# power.net
KiCad netlist of a schematic drawn in Altium Designer
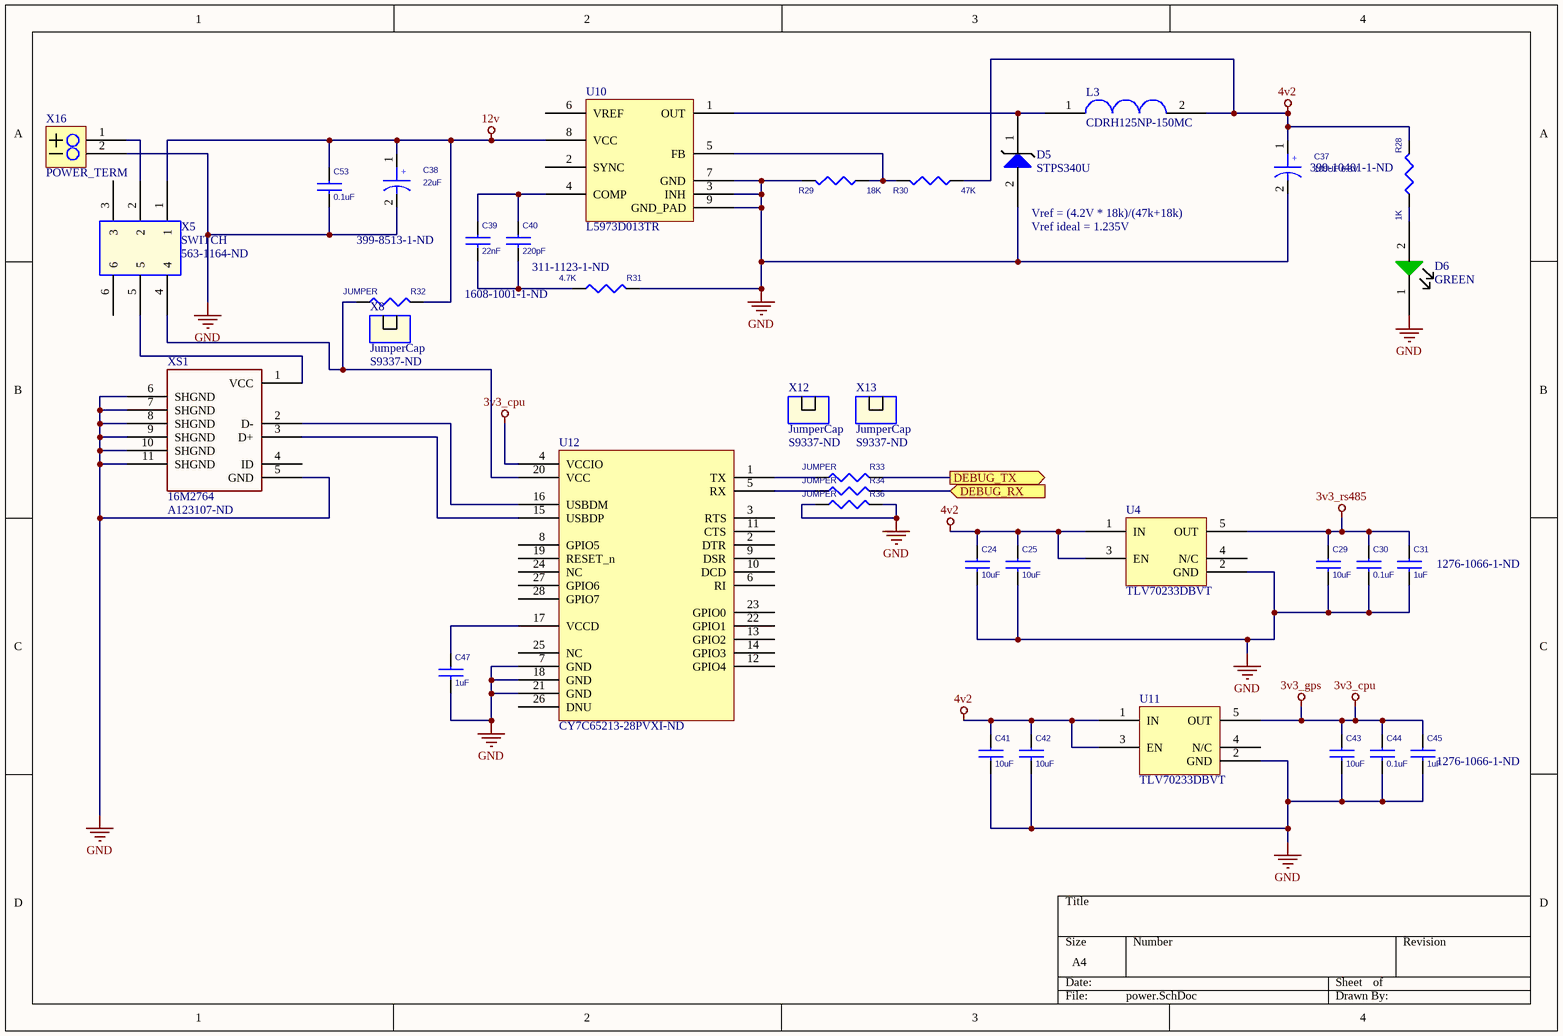
[diagram p0: power.SchDoc]

(export (version "E")
  (design (tool "Eeschema 10.0.6"))
  (components
    (comp (ref "C24")
      (value "10uF")
      (footprint "CAPC2012X09M")
      (description "CAP CER 10UF 16V 20% X5R 0805")
      (libsource (lib "Capacitors") (part "CAP_SMD_10UF_20%"))
    )
    (comp (ref "C25")
      (value "10uF")
      (footprint "CAPC2012X09M")
      (description "CAP CER 10UF 16V 20% X5R 0805")
      (libsource (lib "Capacitors") (part "CAP_SMD_10UF_20%"))
    )
    (comp (ref "C29")
      (value "10uF")
      (footprint "CAPC2012X09M")
      (description "CAP CER 10UF 16V 20% X5R 0805")
      (libsource (lib "Capacitors") (part "CAP_SMD_10UF_20%"))
    )
    (comp (ref "C30")
      (value "0.1uF")
      (footprint "CAPC2012X09M")
      (description "CAP CER 0.1UF 25V 10% X7R 0805")
      (libsource (lib "Capacitors") (part "CAP_SMD_0.1UF_10%"))
    )
    (comp (ref "C31")
      (value "1uF")
      (footprint "CAPC2012X09M")
      (description "MLCC; 1uF; 25V; X7R; ±10%; SMD; 0805;")
      (fields (field (name "SUPPLIER PART NUMBER 1") "1276-1066-1-ND"))
      (libsource (lib "Capacitors") (part "CAP_SMD_1uF_10%"))
    )
    (comp (ref "C37")
      (value "100UF 6.3V")
      (footprint "CAPMP6133X31N")
      (description "CAP 100uF; 6.3V; Case: C; ESR:150mOhm")
      (fields (field (name "SUPPLIER PART NUMBER 1") "399-10401-1-ND"))
      (libsource (lib "Capacitors") (part "CAP_SMD_100UF_10%"))
    )
    (comp (ref "C38")
      (value "22uF")
      (footprint "CAPMP7143X31N")
      (description "CAP SMD 35volts 22uF 10% ESR=300mOhms")
      (fields (field (name "SUPPLIER PART NUMBER 1") "399-8513-1-ND"))
      (libsource (lib "Capacitors") (part "CAP_SMD_22UF_10%"))
    )
    (comp (ref "C39")
      (value "22nF")
      (footprint "CAPC2012X09M")
      (description "CAP 22NF 50V 10% X7R 0805")
      (fields (field (name "SUPPLIER PART NUMBER 1") "1608-1001-1-ND"))
      (libsource (lib "Capacitors") (part "CAP_SMD_22nF_10%"))
    )
    (comp (ref "C40")
      (value "220pF")
      (footprint "CAPC2012X09M")
      (description "CAP 220PF 50V 10%  0805")
      (fields (field (name "SUPPLIER PART NUMBER 1") "311-1123-1-ND"))
      (libsource (lib "Capacitors") (part "CAP_SMD_220pF_10%"))
    )
    (comp (ref "C41")
      (value "10uF")
      (footprint "CAPC2012X09M")
      (description "CAP CER 10UF 16V 20% X5R 0805")
      (libsource (lib "Capacitors") (part "CAP_SMD_10UF_20%"))
    )
    (comp (ref "C42")
      (value "10uF")
      (footprint "CAPC2012X09M")
      (description "CAP CER 10UF 16V 20% X5R 0805")
      (libsource (lib "Capacitors") (part "CAP_SMD_10UF_20%"))
    )
    (comp (ref "C43")
      (value "10uF")
      (footprint "CAPC2012X09M")
      (description "CAP CER 10UF 16V 20% X5R 0805")
      (libsource (lib "Capacitors") (part "CAP_SMD_10UF_20%"))
    )
    (comp (ref "C44")
      (value "0.1uF")
      (footprint "CAPC2012X09M")
      (description "CAP CER 0.1UF 25V 10% X7R 0805")
      (libsource (lib "Capacitors") (part "CAP_SMD_0.1UF_10%"))
    )
    (comp (ref "C45")
      (value "1uF")
      (footprint "CAPC2012X09M")
      (description "MLCC; 1uF; 25V; X7R; ±10%; SMD; 0805;")
      (fields (field (name "SUPPLIER PART NUMBER 1") "1276-1066-1-ND"))
      (libsource (lib "Capacitors") (part "CAP_SMD_1uF_10%"))
    )
    (comp (ref "C47")
      (value "1uF")
      (footprint "CAPC2012X09M")
      (description "MLCC; 1uF; 25V; X7R; ±10%; SMD; 0805;")
      (libsource (lib "Capacitors") (part "CAP_SMD_1uF_10%"))
    )
    (comp (ref "C53")
      (value "0.1uF")
      (footprint "CAPC2012X09M")
      (description "CAP CER 0.1UF 25V 10% X7R 0805")
      (libsource (lib "Capacitors") (part "CAP_SMD_0.1UF_10%"))
    )
    (comp (ref "D5")
      (value "STPS340U")
      (footprint "SODFL535X265-2N")
      (description "DIODE, ZENER, 20V, 3W")
      (libsource (lib "Passive") (part "STPS340U"))
    )
    (comp (ref "D6")
      (value "GREEN")
      (footprint "DIOC2012X11N")
      (libsource (lib "Passive") (part "LED_GREEN"))
    )
    (comp (ref "L3")
      (value "CDRH125NP-150MC")
      (footprint "INDP123123X40N_SUMIDA")
      (libsource (lib "Passive") (part "IND_15uH_3.3A"))
    )
    (comp (ref "R28")
      (value "1K")
      (footprint "RESC2013X06M")
      (description "RES - 1K OHM, 5%, 1/8W, 0805 SMD")
      (libsource (lib "Resistors") (part "RES_SMD_1K_5%"))
    )
    (comp (ref "R29")
      (value "18K")
      (footprint "RESC2013X06M")
      (description "RES 18K OHM 1/8W 1% 0805 SMD")
      (libsource (lib "Resistors") (part "RES_SMD_18K_1%"))
    )
    (comp (ref "R30")
      (value "47K")
      (footprint "RESC2013X06M")
      (description "RES 47K OHM 1/8W 1% 0805")
      (libsource (lib "Resistors") (part "RES_SMD_47K_1%"))
    )
    (comp (ref "R31")
      (value "4.7K")
      (footprint "RESC2013X06M")
      (description "RES 4.7K OHM 1/8W 1% 0805 SMD")
      (libsource (lib "Resistors") (part "RES_SMD_4.7K_1%"))
    )
    (comp (ref "R32")
      (value "JUMPER")
      (footprint "RESC2013X06M_CMEASURE")
      (description "RES 0.0 OHM 1/8W JUMP 0805 SMD")
      (libsource (lib "Resistors") (part "RES_SMD_0_CURRENT"))
    )
    (comp (ref "R33")
      (value "JUMPER")
      (footprint "RESC2013X06M_CMEASURE")
      (description "RES 0.0 OHM 1/8W JUMP 0805 SMD")
      (libsource (lib "Resistors") (part "RES_SMD_0_CURRENT"))
    )
    (comp (ref "R34")
      (value "JUMPER")
      (footprint "RESC2013X06M_CMEASURE")
      (description "RES 0.0 OHM 1/8W JUMP 0805 SMD")
      (libsource (lib "Resistors") (part "RES_SMD_0_CURRENT"))
    )
    (comp (ref "R36")
      (value "JUMPER")
      (footprint "RESC2013X06M_CMEASURE")
      (description "RES 0.0 OHM 1/8W JUMP 0805 SMD")
      (libsource (lib "Resistors") (part "RES_SMD_0_CURRENT"))
    )
    (comp (ref "U4")
      (value "TLV70233DBVT")
      (footprint "SOT95P280X145-5M")
      (libsource (lib "TruthEar") (part "TLV70233DBVT"))
    )
    (comp (ref "U10")
      (value "L5973D013TR")
      (footprint "SOIC127P600X175_HS-9N")
      (description "IC REG BUCK ADJ 2.5A SOIC8")
      (libsource (lib "TruthEar") (part "L5973D013TR"))
    )
    (comp (ref "U11")
      (value "TLV70233DBVT")
      (footprint "SOT95P280X145-5M")
      (libsource (lib "TruthEar") (part "TLV70233DBVT"))
    )
    (comp (ref "U12")
      (value "CY7C65213")
      (footprint "SOP65P780X200-28M")
      (fields (field (name "SUPPLIER PART NUMBER 1") "CY7C65213-28PVXI-ND"))
      (libsource (lib "TruthEar") (part "CY7C65213"))
    )
    (comp (ref "X5")
      (value "SWITCH")
      (footprint "SWITCH")
      (fields (field (name "SUPPLIER PART NUMBER 1") "563-1164-ND"))
      (libsource (lib "TruthEar") (part "SWITCH"))
    )
    (comp (ref "X8")
      (value "JumperCap")
      (description "For BOM only")
      (fields (field (name "SUPPLIER PART NUMBER 1") "S9337-ND"))
      (libsource (lib "TruthEar") (part "JumperCap"))
    )
    (comp (ref "X12")
      (value "JumperCap")
      (description "For BOM only")
      (fields (field (name "SUPPLIER PART NUMBER 1") "S9337-ND"))
      (libsource (lib "TruthEar") (part "JumperCap"))
    )
    (comp (ref "X13")
      (value "JumperCap")
      (description "For BOM only")
      (fields (field (name "SUPPLIER PART NUMBER 1") "S9337-ND"))
      (libsource (lib "TruthEar") (part "JumperCap"))
    )
    (comp (ref "X16")
      (value "POWER_TERM")
      (footprint "PH5")
      (libsource (lib "Connectors") (part "POWER_TERM"))
    )
    (comp (ref "XS1")
      (value "16M2764")
      (footprint "USB_MINI_16M2764")
      (fields (field (name "SUPPLIER PART NUMBER 1") "A123107-ND"))
      (libsource (lib "Connectors") (part "USB_MINI_16M2764"))
    )
  )
  (nets
    (net (code "1") (name "/DEBUG_RX") (class "Default")
      (node (ref "R34") (pin "2") (pinfunction "2_2") (pintype "passive"))
    )
    (net (code "2") (name "/DEBUG_TX") (class "Default")
      (node (ref "R33") (pin "2") (pinfunction "2_2") (pintype "passive"))
    )
    (net (code "3") (name "3v3_cpu") (class "Default")
      (node (ref "C43") (pin "1") (pinfunction "1_1") (pintype "passive"))
      (node (ref "C44") (pin "1") (pinfunction "1_1") (pintype "passive"))
      (node (ref "C45") (pin "1") (pinfunction "1_1") (pintype "passive"))
      (node (ref "U11") (pin "5") (pinfunction "OUT_5") (pintype "passive"))
      (node (ref "U12") (pin "4") (pinfunction "VCCIO_4") (pintype "power_in"))
    )
    (net (code "4") (name "3v3_rs485") (class "Default")
      (node (ref "C29") (pin "1") (pinfunction "1_1") (pintype "passive"))
      (node (ref "C30") (pin "1") (pinfunction "1_1") (pintype "passive"))
      (node (ref "C31") (pin "1") (pinfunction "1_1") (pintype "passive"))
      (node (ref "U4") (pin "5") (pinfunction "OUT_5") (pintype "passive"))
    )
    (net (code "5") (name "4v2") (class "Default")
      (node (ref "C24") (pin "1") (pinfunction "1_1") (pintype "passive"))
      (node (ref "C25") (pin "1") (pinfunction "1_1") (pintype "passive"))
      (node (ref "C37") (pin "1") (pinfunction "1_1") (pintype "passive"))
      (node (ref "C41") (pin "1") (pinfunction "1_1") (pintype "passive"))
      (node (ref "C42") (pin "1") (pinfunction "1_1") (pintype "passive"))
      (node (ref "L3") (pin "2") (pinfunction "2_2") (pintype "passive"))
      (node (ref "R28") (pin "2") (pinfunction "2_2") (pintype "passive"))
      (node (ref "R30") (pin "1") (pinfunction "1_1") (pintype "passive"))
      (node (ref "U11") (pin "1") (pinfunction "IN_1") (pintype "passive"))
      (node (ref "U11") (pin "3") (pinfunction "EN_3") (pintype "passive"))
      (node (ref "U4") (pin "1") (pinfunction "IN_1") (pintype "passive"))
      (node (ref "U4") (pin "3") (pinfunction "EN_3") (pintype "passive"))
    )
    (net (code "6") (name "12v") (class "Default")
      (node (ref "C38") (pin "1") (pinfunction "1_1") (pintype "passive"))
      (node (ref "C53") (pin "1") (pinfunction "1_1") (pintype "passive"))
      (node (ref "R32") (pin "2") (pinfunction "2_2") (pintype "passive"))
      (node (ref "U10") (pin "8") (pinfunction "VCC_8") (pintype "passive"))
      (node (ref "X5") (pin "1") (pinfunction "1_1") (pintype "passive"))
    )
    (net (code "7") (name "GND") (class "Default")
      (node (ref "C24") (pin "2") (pinfunction "2_2") (pintype "passive"))
      (node (ref "C25") (pin "2") (pinfunction "2_2") (pintype "passive"))
      (node (ref "C29") (pin "2") (pinfunction "2_2") (pintype "passive"))
      (node (ref "C30") (pin "2") (pinfunction "2_2") (pintype "passive"))
      (node (ref "C31") (pin "2") (pinfunction "2_2") (pintype "passive"))
      (node (ref "C37") (pin "2") (pinfunction "2_2") (pintype "passive"))
      (node (ref "C38") (pin "2") (pinfunction "2_2") (pintype "passive"))
      (node (ref "C41") (pin "2") (pinfunction "2_2") (pintype "passive"))
      (node (ref "C42") (pin "2") (pinfunction "2_2") (pintype "passive"))
      (node (ref "C43") (pin "2") (pinfunction "2_2") (pintype "passive"))
      (node (ref "C44") (pin "2") (pinfunction "2_2") (pintype "passive"))
      (node (ref "C45") (pin "2") (pinfunction "2_2") (pintype "passive"))
      (node (ref "C47") (pin "2") (pinfunction "2_2") (pintype "passive"))
      (node (ref "C53") (pin "2") (pinfunction "2_2") (pintype "passive"))
      (node (ref "D5") (pin "2") (pinfunction "A_2") (pintype "passive"))
      (node (ref "D6") (pin "1") (pinfunction "C_1") (pintype "passive"))
      (node (ref "R29") (pin "2") (pinfunction "2_2") (pintype "passive"))
      (node (ref "R31") (pin "2") (pinfunction "2_2") (pintype "passive"))
      (node (ref "R36") (pin "1") (pinfunction "1_1") (pintype "passive"))
      (node (ref "R36") (pin "2") (pinfunction "2_2") (pintype "passive"))
      (node (ref "U10") (pin "3") (pinfunction "INH_3") (pintype "passive"))
      (node (ref "U10") (pin "7") (pinfunction "GND_7") (pintype "passive"))
      (node (ref "U10") (pin "9") (pinfunction "GND_PAD_9") (pintype "passive"))
      (node (ref "U11") (pin "2") (pinfunction "GND_2") (pintype "passive"))
      (node (ref "U12") (pin "18") (pinfunction "GND_18") (pintype "power_in"))
      (node (ref "U12") (pin "21") (pinfunction "GND_21") (pintype "power_in"))
      (node (ref "U12") (pin "7") (pinfunction "GND_7") (pintype "power_in"))
      (node (ref "U4") (pin "2") (pinfunction "GND_2") (pintype "passive"))
      (node (ref "X16") (pin "2") (pinfunction "2_2") (pintype "passive"))
      (node (ref "XS1") (pin "10") (pinfunction "SHGND_10") (pintype "passive"))
      (node (ref "XS1") (pin "11") (pinfunction "SHGND_11") (pintype "passive"))
      (node (ref "XS1") (pin "5") (pinfunction "GND_5") (pintype "passive"))
      (node (ref "XS1") (pin "6") (pinfunction "SHGND_6") (pintype "passive"))
      (node (ref "XS1") (pin "7") (pinfunction "SHGND_7") (pintype "passive"))
      (node (ref "XS1") (pin "8") (pinfunction "SHGND_8") (pintype "passive"))
      (node (ref "XS1") (pin "9") (pinfunction "SHGND_9") (pintype "passive"))
    )
    (net (code "8") (name "Net-(C39-Pad2)") (class "Default")
      (node (ref "C39") (pin "2") (pinfunction "2_2") (pintype "passive"))
      (node (ref "C40") (pin "2") (pinfunction "2_2") (pintype "passive"))
      (node (ref "R31") (pin "1") (pinfunction "1_1") (pintype "passive"))
    )
    (net (code "9") (name "Net-(D5-C)") (class "Default")
      (node (ref "D5") (pin "1") (pinfunction "C_1") (pintype "passive"))
      (node (ref "L3") (pin "1") (pinfunction "1_1") (pintype "passive"))
      (node (ref "U10") (pin "1") (pinfunction "OUT_1") (pintype "passive"))
    )
    (net (code "10") (name "Net-(D6-A)") (class "Default")
      (node (ref "D6") (pin "2") (pinfunction "A_2") (pintype "passive"))
      (node (ref "R28") (pin "1") (pinfunction "1_1") (pintype "passive"))
    )
    (net (code "11") (name "Net-(U10-COMP)") (class "Default")
      (node (ref "C39") (pin "1") (pinfunction "1_1") (pintype "passive"))
      (node (ref "C40") (pin "1") (pinfunction "1_1") (pintype "passive"))
      (node (ref "U10") (pin "4") (pinfunction "COMP_4") (pintype "passive"))
    )
    (net (code "12") (name "Net-(U10-FB)") (class "Default")
      (node (ref "R29") (pin "1") (pinfunction "1_1") (pintype "passive"))
      (node (ref "R30") (pin "2") (pinfunction "2_2") (pintype "passive"))
      (node (ref "U10") (pin "5") (pinfunction "FB_5") (pintype "passive"))
    )
    (net (code "13") (name "Net-(U12-RX)") (class "Default")
      (node (ref "R34") (pin "1") (pinfunction "1_1") (pintype "passive"))
      (node (ref "U12") (pin "5") (pinfunction "RX_5") (pintype "power_in"))
    )
    (net (code "14") (name "Net-(U12-TX)") (class "Default")
      (node (ref "R33") (pin "1") (pinfunction "1_1") (pintype "passive"))
      (node (ref "U12") (pin "1") (pinfunction "TX_1") (pintype "power_in"))
    )
    (net (code "15") (name "Net-(U12-USBDM)") (class "Default")
      (node (ref "U12") (pin "16") (pinfunction "USBDM_16") (pintype "power_in"))
      (node (ref "XS1") (pin "2") (pinfunction "D-_2") (pintype "passive"))
    )
    (net (code "16") (name "Net-(U12-USBDP)") (class "Default")
      (node (ref "U12") (pin "15") (pinfunction "USBDP_15") (pintype "power_in"))
      (node (ref "XS1") (pin "3") (pinfunction "D+_3") (pintype "passive"))
    )
    (net (code "17") (name "Net-(U12-VCC)") (class "Default")
      (node (ref "R32") (pin "1") (pinfunction "1_1") (pintype "passive"))
      (node (ref "U12") (pin "20") (pinfunction "VCC_20") (pintype "power_in"))
      (node (ref "X5") (pin "4") (pinfunction "4_4") (pintype "passive"))
    )
    (net (code "18") (name "Net-(U12-VCCD)") (class "Default")
      (node (ref "C47") (pin "1") (pinfunction "1_1") (pintype "passive"))
      (node (ref "U12") (pin "17") (pinfunction "VCCD_17") (pintype "power_in"))
    )
    (net (code "19") (name "Net-(X16-Pad1)") (class "Default")
      (node (ref "X16") (pin "1") (pinfunction "1_1") (pintype "passive"))
      (node (ref "X5") (pin "2") (pinfunction "2_2") (pintype "passive"))
    )
    (net (code "20") (name "Net-(XS1-VCC)") (class "Default")
      (node (ref "X5") (pin "5") (pinfunction "5_5") (pintype "passive"))
      (node (ref "XS1") (pin "1") (pinfunction "VCC_1") (pintype "passive"))
    )
    (net (code "21") (name "unconnected-(U4-N{slash}C-Pad4)") (class "Default")
      (node (ref "U4") (pin "4") (pinfunction "N/C_4") (pintype "passive"))
    )
    (net (code "22") (name "unconnected-(U10-SYNC-Pad2)") (class "Default")
      (node (ref "U10") (pin "2") (pinfunction "SYNC_2") (pintype "passive"))
    )
    (net (code "23") (name "unconnected-(U10-VREF-Pad6)") (class "Default")
      (node (ref "U10") (pin "6") (pinfunction "VREF_6") (pintype "passive"))
    )
    (net (code "24") (name "unconnected-(U11-N{slash}C-Pad4)") (class "Default")
      (node (ref "U11") (pin "4") (pinfunction "N/C_4") (pintype "passive"))
    )
    (net (code "25") (name "unconnected-(U12-CTS-Pad11)") (class "Default")
      (node (ref "U12") (pin "11") (pinfunction "CTS_11") (pintype "power_in"))
    )
    (net (code "26") (name "unconnected-(U12-DCD-Pad10)") (class "Default")
      (node (ref "U12") (pin "10") (pinfunction "DCD_10") (pintype "power_in"))
    )
    (net (code "27") (name "unconnected-(U12-DNU-Pad26)") (class "Default")
      (node (ref "U12") (pin "26") (pinfunction "DNU_26") (pintype "power_in"))
    )
    (net (code "28") (name "unconnected-(U12-DSR-Pad9)") (class "Default")
      (node (ref "U12") (pin "9") (pinfunction "DSR_9") (pintype "power_in"))
    )
    (net (code "29") (name "unconnected-(U12-DTR-Pad2)") (class "Default")
      (node (ref "U12") (pin "2") (pinfunction "DTR_2") (pintype "power_in"))
    )
    (net (code "30") (name "unconnected-(U12-GPIO0-Pad23)") (class "Default")
      (node (ref "U12") (pin "23") (pinfunction "GPIO0_23") (pintype "power_in"))
    )
    (net (code "31") (name "unconnected-(U12-GPIO1-Pad22)") (class "Default")
      (node (ref "U12") (pin "22") (pinfunction "GPIO1_22") (pintype "power_in"))
    )
    (net (code "32") (name "unconnected-(U12-GPIO2-Pad13)") (class "Default")
      (node (ref "U12") (pin "13") (pinfunction "GPIO2_13") (pintype "power_in"))
    )
    (net (code "33") (name "unconnected-(U12-GPIO3-Pad14)") (class "Default")
      (node (ref "U12") (pin "14") (pinfunction "GPIO3_14") (pintype "power_in"))
    )
    (net (code "34") (name "unconnected-(U12-GPIO4-Pad12)") (class "Default")
      (node (ref "U12") (pin "12") (pinfunction "GPIO4_12") (pintype "power_in"))
    )
    (net (code "35") (name "unconnected-(U12-GPIO5-Pad8)") (class "Default")
      (node (ref "U12") (pin "8") (pinfunction "GPIO5_8") (pintype "power_in"))
    )
    (net (code "36") (name "unconnected-(U12-GPIO6-Pad27)") (class "Default")
      (node (ref "U12") (pin "27") (pinfunction "GPIO6_27") (pintype "power_in"))
    )
    (net (code "37") (name "unconnected-(U12-GPIO7-Pad28)") (class "Default")
      (node (ref "U12") (pin "28") (pinfunction "GPIO7_28") (pintype "power_in"))
    )
    (net (code "38") (name "unconnected-(U12-NC-Pad24)") (class "Default")
      (node (ref "U12") (pin "24") (pinfunction "NC_24") (pintype "power_in"))
    )
    (net (code "39") (name "unconnected-(U12-NC-Pad25)") (class "Default")
      (node (ref "U12") (pin "25") (pinfunction "NC_25") (pintype "power_in"))
    )
    (net (code "40") (name "unconnected-(U12-RESET_n-Pad19)") (class "Default")
      (node (ref "U12") (pin "19") (pinfunction "RESET_n_19") (pintype "power_in"))
    )
    (net (code "41") (name "unconnected-(U12-RI-Pad6)") (class "Default")
      (node (ref "U12") (pin "6") (pinfunction "RI_6") (pintype "power_in"))
    )
    (net (code "42") (name "unconnected-(U12-RTS-Pad3)") (class "Default")
      (node (ref "U12") (pin "3") (pinfunction "RTS_3") (pintype "power_in"))
    )
    (net (code "43") (name "unconnected-(X5-Pad3)") (class "Default")
      (node (ref "X5") (pin "3") (pinfunction "3_3") (pintype "passive"))
    )
    (net (code "44") (name "unconnected-(X5-Pad6)") (class "Default")
      (node (ref "X5") (pin "6") (pinfunction "6_6") (pintype "passive"))
    )
    (net (code "45") (name "unconnected-(XS1-ID-Pad4)") (class "Default")
      (node (ref "XS1") (pin "4") (pinfunction "ID_4") (pintype "passive"))
    )
  )
)
